# Conex_o_Motor.net
KiCad netlist of a schematic drawn in EAGLE
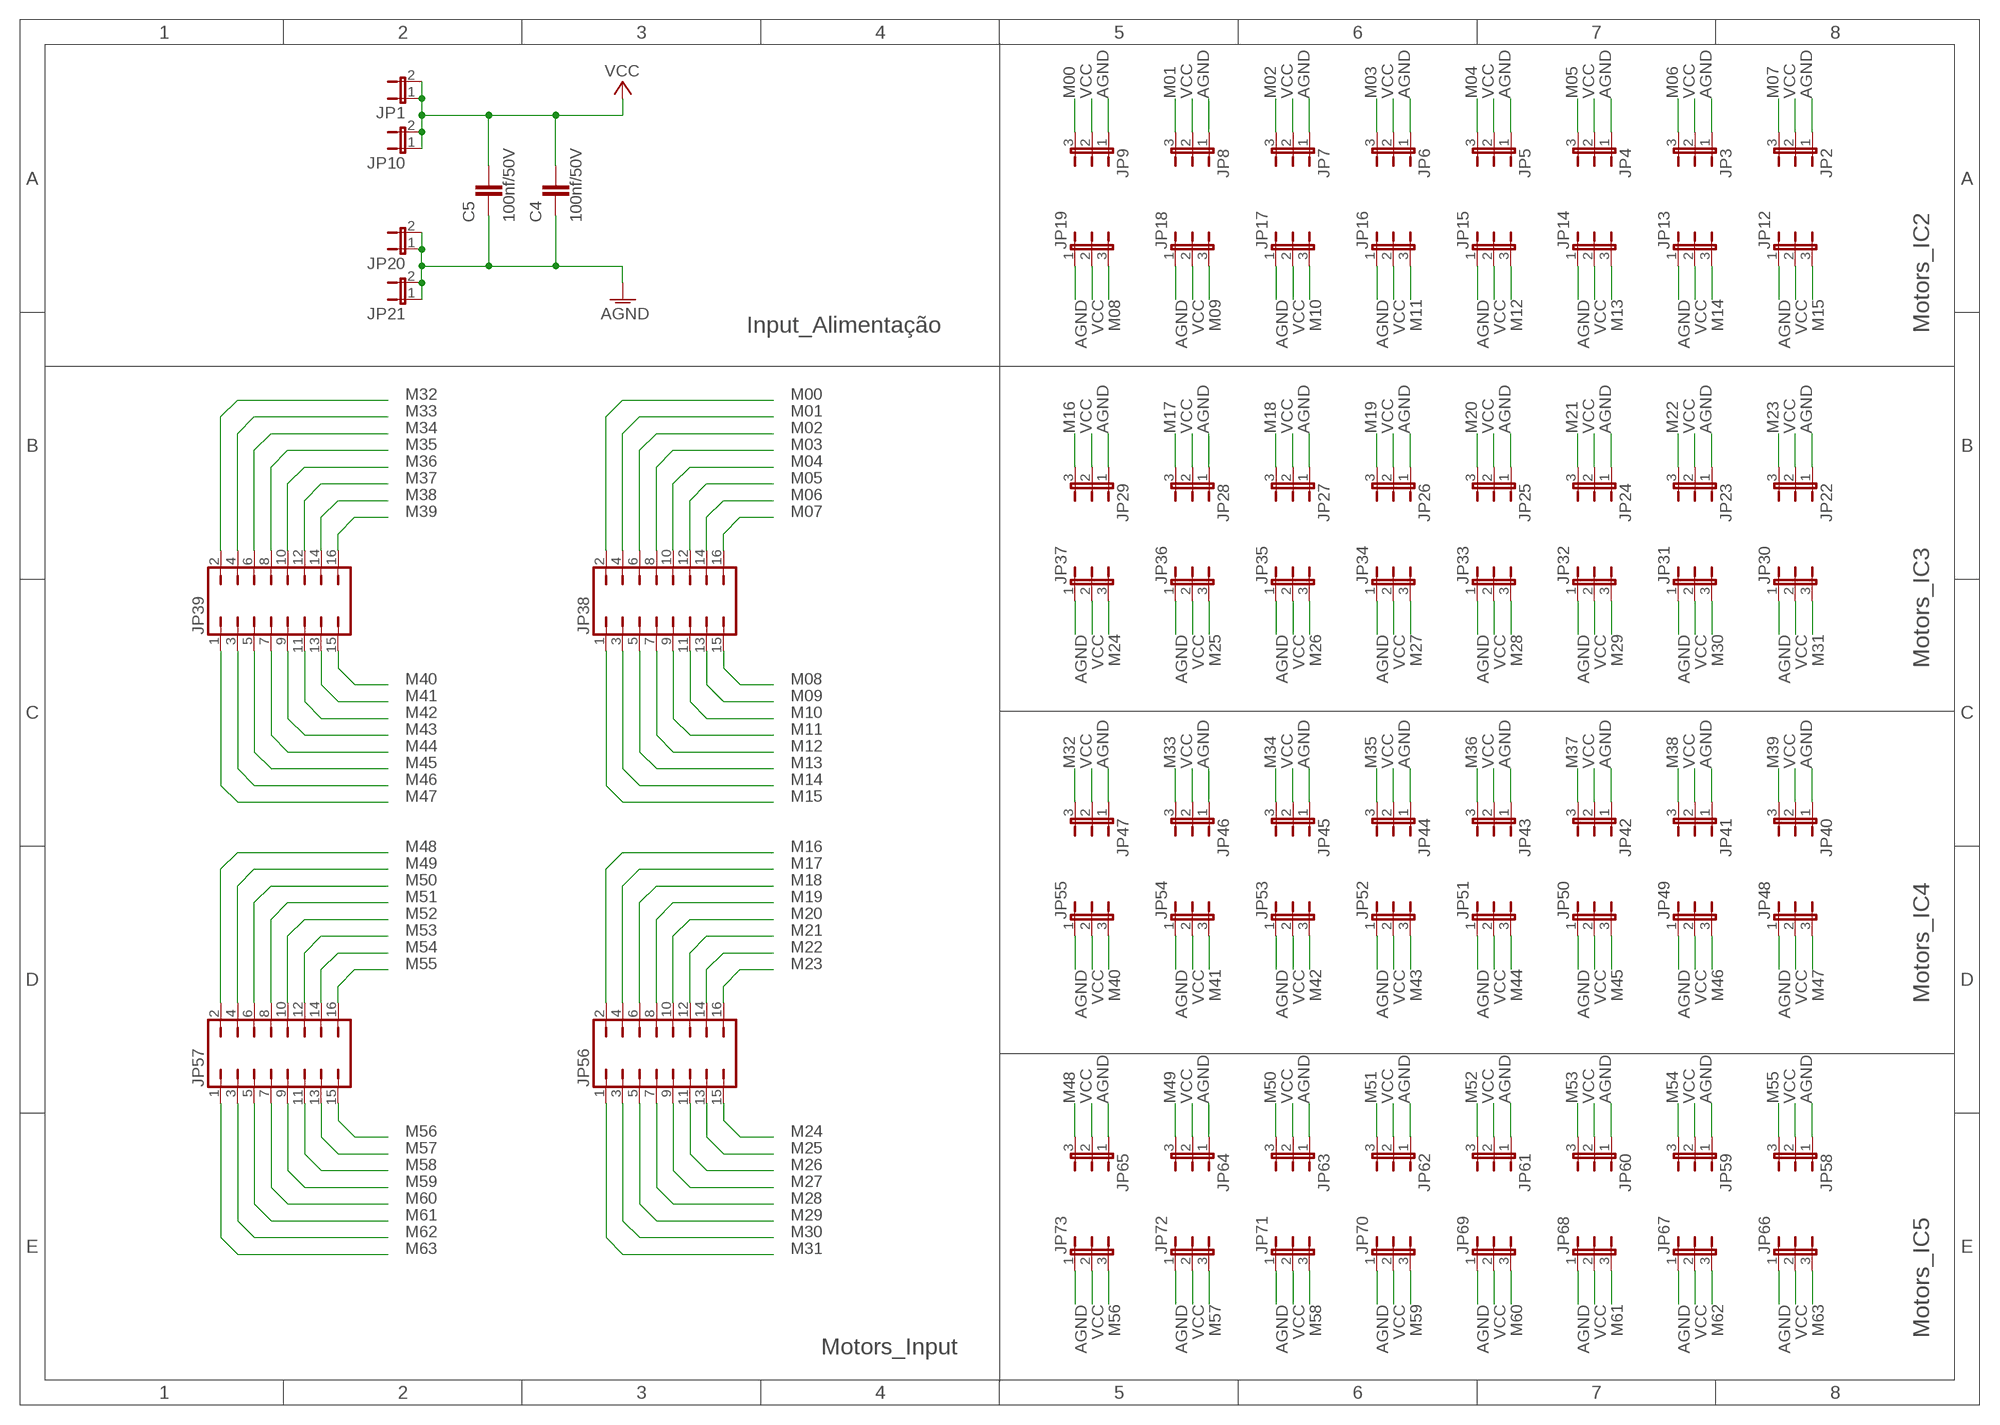
[diagram p0: schematic, sheet 1]

(export (version "E")
  (design (tool "Eeschema 10.0.6"))
  (components
    (comp (ref "C4")
      (value "100nf/50V")
      (footprint "eagle-import:C0805K")
      (libsource (lib "eagle-import") (part "C-EUC0805K"))
    )
    (comp (ref "C5")
      (value "100nf/50V")
      (footprint "eagle-import:C0805K")
      (libsource (lib "eagle-import") (part "C-EUC0805K"))
    )
    (comp (ref "JP1")
      (value "JP1E")
      (footprint "eagle-import:JP1")
      (libsource (lib "eagle-import") (part "JP1E"))
    )
    (comp (ref "JP2")
      (value "JP2E")
      (footprint "eagle-import:JP2")
      (libsource (lib "eagle-import") (part "JP2E"))
    )
    (comp (ref "JP3")
      (value "JP2E")
      (footprint "eagle-import:JP2")
      (libsource (lib "eagle-import") (part "JP2E"))
    )
    (comp (ref "JP4")
      (value "JP2E")
      (footprint "eagle-import:JP2")
      (libsource (lib "eagle-import") (part "JP2E"))
    )
    (comp (ref "JP5")
      (value "JP2E")
      (footprint "eagle-import:JP2")
      (libsource (lib "eagle-import") (part "JP2E"))
    )
    (comp (ref "JP6")
      (value "JP2E")
      (footprint "eagle-import:JP2")
      (libsource (lib "eagle-import") (part "JP2E"))
    )
    (comp (ref "JP7")
      (value "JP2E")
      (footprint "eagle-import:JP2")
      (libsource (lib "eagle-import") (part "JP2E"))
    )
    (comp (ref "JP8")
      (value "JP2E")
      (footprint "eagle-import:JP2")
      (libsource (lib "eagle-import") (part "JP2E"))
    )
    (comp (ref "JP9")
      (value "JP2E")
      (footprint "eagle-import:JP2")
      (libsource (lib "eagle-import") (part "JP2E"))
    )
    (comp (ref "JP10")
      (value "JP1E")
      (footprint "eagle-import:JP1")
      (libsource (lib "eagle-import") (part "JP1E"))
    )
    (comp (ref "JP12")
      (value "JP2E")
      (footprint "eagle-import:JP2")
      (libsource (lib "eagle-import") (part "JP2E"))
    )
    (comp (ref "JP13")
      (value "JP2E")
      (footprint "eagle-import:JP2")
      (libsource (lib "eagle-import") (part "JP2E"))
    )
    (comp (ref "JP14")
      (value "JP2E")
      (footprint "eagle-import:JP2")
      (libsource (lib "eagle-import") (part "JP2E"))
    )
    (comp (ref "JP15")
      (value "JP2E")
      (footprint "eagle-import:JP2")
      (libsource (lib "eagle-import") (part "JP2E"))
    )
    (comp (ref "JP16")
      (value "JP2E")
      (footprint "eagle-import:JP2")
      (libsource (lib "eagle-import") (part "JP2E"))
    )
    (comp (ref "JP17")
      (value "JP2E")
      (footprint "eagle-import:JP2")
      (libsource (lib "eagle-import") (part "JP2E"))
    )
    (comp (ref "JP18")
      (value "JP2E")
      (footprint "eagle-import:JP2")
      (libsource (lib "eagle-import") (part "JP2E"))
    )
    (comp (ref "JP19")
      (value "JP2E")
      (footprint "eagle-import:JP2")
      (libsource (lib "eagle-import") (part "JP2E"))
    )
    (comp (ref "JP20")
      (value "JP1E")
      (footprint "eagle-import:JP1")
      (libsource (lib "eagle-import") (part "JP1E"))
    )
    (comp (ref "JP21")
      (value "JP1E")
      (footprint "eagle-import:JP1")
      (libsource (lib "eagle-import") (part "JP1E"))
    )
    (comp (ref "JP22")
      (value "JP2E")
      (footprint "eagle-import:JP2")
      (libsource (lib "eagle-import") (part "JP2E"))
    )
    (comp (ref "JP23")
      (value "JP2E")
      (footprint "eagle-import:JP2")
      (libsource (lib "eagle-import") (part "JP2E"))
    )
    (comp (ref "JP24")
      (value "JP2E")
      (footprint "eagle-import:JP2")
      (libsource (lib "eagle-import") (part "JP2E"))
    )
    (comp (ref "JP25")
      (value "JP2E")
      (footprint "eagle-import:JP2")
      (libsource (lib "eagle-import") (part "JP2E"))
    )
    (comp (ref "JP26")
      (value "JP2E")
      (footprint "eagle-import:JP2")
      (libsource (lib "eagle-import") (part "JP2E"))
    )
    (comp (ref "JP27")
      (value "JP2E")
      (footprint "eagle-import:JP2")
      (libsource (lib "eagle-import") (part "JP2E"))
    )
    (comp (ref "JP28")
      (value "JP2E")
      (footprint "eagle-import:JP2")
      (libsource (lib "eagle-import") (part "JP2E"))
    )
    (comp (ref "JP29")
      (value "JP2E")
      (footprint "eagle-import:JP2")
      (libsource (lib "eagle-import") (part "JP2E"))
    )
    (comp (ref "JP30")
      (value "JP2E")
      (footprint "eagle-import:JP2")
      (libsource (lib "eagle-import") (part "JP2E"))
    )
    (comp (ref "JP31")
      (value "JP2E")
      (footprint "eagle-import:JP2")
      (libsource (lib "eagle-import") (part "JP2E"))
    )
    (comp (ref "JP32")
      (value "JP2E")
      (footprint "eagle-import:JP2")
      (libsource (lib "eagle-import") (part "JP2E"))
    )
    (comp (ref "JP33")
      (value "JP2E")
      (footprint "eagle-import:JP2")
      (libsource (lib "eagle-import") (part "JP2E"))
    )
    (comp (ref "JP34")
      (value "JP2E")
      (footprint "eagle-import:JP2")
      (libsource (lib "eagle-import") (part "JP2E"))
    )
    (comp (ref "JP35")
      (value "JP2E")
      (footprint "eagle-import:JP2")
      (libsource (lib "eagle-import") (part "JP2E"))
    )
    (comp (ref "JP36")
      (value "JP2E")
      (footprint "eagle-import:JP2")
      (libsource (lib "eagle-import") (part "JP2E"))
    )
    (comp (ref "JP37")
      (value "JP2E")
      (footprint "eagle-import:JP2")
      (libsource (lib "eagle-import") (part "JP2E"))
    )
    (comp (ref "JP38")
      (value "JP8Q")
      (footprint "eagle-import:JP8Q")
      (libsource (lib "eagle-import") (part "JP8Q"))
    )
    (comp (ref "JP39")
      (value "JP8Q")
      (footprint "eagle-import:JP8Q")
      (libsource (lib "eagle-import") (part "JP8Q"))
    )
    (comp (ref "JP40")
      (value "JP2E")
      (footprint "eagle-import:JP2")
      (libsource (lib "eagle-import") (part "JP2E"))
    )
    (comp (ref "JP41")
      (value "JP2E")
      (footprint "eagle-import:JP2")
      (libsource (lib "eagle-import") (part "JP2E"))
    )
    (comp (ref "JP42")
      (value "JP2E")
      (footprint "eagle-import:JP2")
      (libsource (lib "eagle-import") (part "JP2E"))
    )
    (comp (ref "JP43")
      (value "JP2E")
      (footprint "eagle-import:JP2")
      (libsource (lib "eagle-import") (part "JP2E"))
    )
    (comp (ref "JP44")
      (value "JP2E")
      (footprint "eagle-import:JP2")
      (libsource (lib "eagle-import") (part "JP2E"))
    )
    (comp (ref "JP45")
      (value "JP2E")
      (footprint "eagle-import:JP2")
      (libsource (lib "eagle-import") (part "JP2E"))
    )
    (comp (ref "JP46")
      (value "JP2E")
      (footprint "eagle-import:JP2")
      (libsource (lib "eagle-import") (part "JP2E"))
    )
    (comp (ref "JP47")
      (value "JP2E")
      (footprint "eagle-import:JP2")
      (libsource (lib "eagle-import") (part "JP2E"))
    )
    (comp (ref "JP48")
      (value "JP2E")
      (footprint "eagle-import:JP2")
      (libsource (lib "eagle-import") (part "JP2E"))
    )
    (comp (ref "JP49")
      (value "JP2E")
      (footprint "eagle-import:JP2")
      (libsource (lib "eagle-import") (part "JP2E"))
    )
    (comp (ref "JP50")
      (value "JP2E")
      (footprint "eagle-import:JP2")
      (libsource (lib "eagle-import") (part "JP2E"))
    )
    (comp (ref "JP51")
      (value "JP2E")
      (footprint "eagle-import:JP2")
      (libsource (lib "eagle-import") (part "JP2E"))
    )
    (comp (ref "JP52")
      (value "JP2E")
      (footprint "eagle-import:JP2")
      (libsource (lib "eagle-import") (part "JP2E"))
    )
    (comp (ref "JP53")
      (value "JP2E")
      (footprint "eagle-import:JP2")
      (libsource (lib "eagle-import") (part "JP2E"))
    )
    (comp (ref "JP54")
      (value "JP2E")
      (footprint "eagle-import:JP2")
      (libsource (lib "eagle-import") (part "JP2E"))
    )
    (comp (ref "JP55")
      (value "JP2E")
      (footprint "eagle-import:JP2")
      (libsource (lib "eagle-import") (part "JP2E"))
    )
    (comp (ref "JP56")
      (value "JP8Q")
      (footprint "eagle-import:JP8Q")
      (libsource (lib "eagle-import") (part "JP8Q"))
    )
    (comp (ref "JP57")
      (value "JP8Q")
      (footprint "eagle-import:JP8Q")
      (libsource (lib "eagle-import") (part "JP8Q"))
    )
    (comp (ref "JP58")
      (value "JP2E")
      (footprint "eagle-import:JP2")
      (libsource (lib "eagle-import") (part "JP2E"))
    )
    (comp (ref "JP59")
      (value "JP2E")
      (footprint "eagle-import:JP2")
      (libsource (lib "eagle-import") (part "JP2E"))
    )
    (comp (ref "JP60")
      (value "JP2E")
      (footprint "eagle-import:JP2")
      (libsource (lib "eagle-import") (part "JP2E"))
    )
    (comp (ref "JP61")
      (value "JP2E")
      (footprint "eagle-import:JP2")
      (libsource (lib "eagle-import") (part "JP2E"))
    )
    (comp (ref "JP62")
      (value "JP2E")
      (footprint "eagle-import:JP2")
      (libsource (lib "eagle-import") (part "JP2E"))
    )
    (comp (ref "JP63")
      (value "JP2E")
      (footprint "eagle-import:JP2")
      (libsource (lib "eagle-import") (part "JP2E"))
    )
    (comp (ref "JP64")
      (value "JP2E")
      (footprint "eagle-import:JP2")
      (libsource (lib "eagle-import") (part "JP2E"))
    )
    (comp (ref "JP65")
      (value "JP2E")
      (footprint "eagle-import:JP2")
      (libsource (lib "eagle-import") (part "JP2E"))
    )
    (comp (ref "JP66")
      (value "JP2E")
      (footprint "eagle-import:JP2")
      (libsource (lib "eagle-import") (part "JP2E"))
    )
    (comp (ref "JP67")
      (value "JP2E")
      (footprint "eagle-import:JP2")
      (libsource (lib "eagle-import") (part "JP2E"))
    )
    (comp (ref "JP68")
      (value "JP2E")
      (footprint "eagle-import:JP2")
      (libsource (lib "eagle-import") (part "JP2E"))
    )
    (comp (ref "JP69")
      (value "JP2E")
      (footprint "eagle-import:JP2")
      (libsource (lib "eagle-import") (part "JP2E"))
    )
    (comp (ref "JP70")
      (value "JP2E")
      (footprint "eagle-import:JP2")
      (libsource (lib "eagle-import") (part "JP2E"))
    )
    (comp (ref "JP71")
      (value "JP2E")
      (footprint "eagle-import:JP2")
      (libsource (lib "eagle-import") (part "JP2E"))
    )
    (comp (ref "JP72")
      (value "JP2E")
      (footprint "eagle-import:JP2")
      (libsource (lib "eagle-import") (part "JP2E"))
    )
    (comp (ref "JP73")
      (value "JP2E")
      (footprint "eagle-import:JP2")
      (libsource (lib "eagle-import") (part "JP2E"))
    )
  )
  (nets
    (net (code "1") (name "/M00") (class "Default")
      (node (ref "JP38") (pin "2") (pinfunction "2_2") (pintype "passive"))
      (node (ref "JP9") (pin "3") (pinfunction "3_3") (pintype "passive"))
    )
    (net (code "2") (name "/M01") (class "Default")
      (node (ref "JP38") (pin "4") (pinfunction "4_4") (pintype "passive"))
      (node (ref "JP8") (pin "3") (pinfunction "3_3") (pintype "passive"))
    )
    (net (code "3") (name "/M02") (class "Default")
      (node (ref "JP38") (pin "6") (pinfunction "6_6") (pintype "passive"))
      (node (ref "JP7") (pin "3") (pinfunction "3_3") (pintype "passive"))
    )
    (net (code "4") (name "/M03") (class "Default")
      (node (ref "JP38") (pin "8") (pinfunction "8_8") (pintype "passive"))
      (node (ref "JP6") (pin "3") (pinfunction "3_3") (pintype "passive"))
    )
    (net (code "5") (name "/M04") (class "Default")
      (node (ref "JP38") (pin "10") (pinfunction "10_10") (pintype "passive"))
      (node (ref "JP5") (pin "3") (pinfunction "3_3") (pintype "passive"))
    )
    (net (code "6") (name "/M05") (class "Default")
      (node (ref "JP38") (pin "12") (pinfunction "12_12") (pintype "passive"))
      (node (ref "JP4") (pin "3") (pinfunction "3_3") (pintype "passive"))
    )
    (net (code "7") (name "/M06") (class "Default")
      (node (ref "JP3") (pin "3") (pinfunction "3_3") (pintype "passive"))
      (node (ref "JP38") (pin "14") (pinfunction "14_14") (pintype "passive"))
    )
    (net (code "8") (name "/M07") (class "Default")
      (node (ref "JP2") (pin "3") (pinfunction "3_3") (pintype "passive"))
      (node (ref "JP38") (pin "16") (pinfunction "16_16") (pintype "passive"))
    )
    (net (code "9") (name "/M08") (class "Default")
      (node (ref "JP19") (pin "3") (pinfunction "3_3") (pintype "passive"))
      (node (ref "JP38") (pin "15") (pinfunction "15_15") (pintype "passive"))
    )
    (net (code "10") (name "/M09") (class "Default")
      (node (ref "JP18") (pin "3") (pinfunction "3_3") (pintype "passive"))
      (node (ref "JP38") (pin "13") (pinfunction "13_13") (pintype "passive"))
    )
    (net (code "11") (name "/M10") (class "Default")
      (node (ref "JP17") (pin "3") (pinfunction "3_3") (pintype "passive"))
      (node (ref "JP38") (pin "11") (pinfunction "11_11") (pintype "passive"))
    )
    (net (code "12") (name "/M11") (class "Default")
      (node (ref "JP16") (pin "3") (pinfunction "3_3") (pintype "passive"))
      (node (ref "JP38") (pin "9") (pinfunction "9_9") (pintype "passive"))
    )
    (net (code "13") (name "/M12") (class "Default")
      (node (ref "JP15") (pin "3") (pinfunction "3_3") (pintype "passive"))
      (node (ref "JP38") (pin "7") (pinfunction "7_7") (pintype "passive"))
    )
    (net (code "14") (name "/M13") (class "Default")
      (node (ref "JP14") (pin "3") (pinfunction "3_3") (pintype "passive"))
      (node (ref "JP38") (pin "5") (pinfunction "5_5") (pintype "passive"))
    )
    (net (code "15") (name "/M14") (class "Default")
      (node (ref "JP13") (pin "3") (pinfunction "3_3") (pintype "passive"))
      (node (ref "JP38") (pin "3") (pinfunction "3_3") (pintype "passive"))
    )
    (net (code "16") (name "/M15") (class "Default")
      (node (ref "JP12") (pin "3") (pinfunction "3_3") (pintype "passive"))
      (node (ref "JP38") (pin "1") (pinfunction "1_1") (pintype "passive"))
    )
    (net (code "17") (name "/M16") (class "Default")
      (node (ref "JP29") (pin "3") (pinfunction "3_3") (pintype "passive"))
      (node (ref "JP56") (pin "2") (pinfunction "2_2") (pintype "passive"))
    )
    (net (code "18") (name "/M17") (class "Default")
      (node (ref "JP28") (pin "3") (pinfunction "3_3") (pintype "passive"))
      (node (ref "JP56") (pin "4") (pinfunction "4_4") (pintype "passive"))
    )
    (net (code "19") (name "/M18") (class "Default")
      (node (ref "JP27") (pin "3") (pinfunction "3_3") (pintype "passive"))
      (node (ref "JP56") (pin "6") (pinfunction "6_6") (pintype "passive"))
    )
    (net (code "20") (name "/M19") (class "Default")
      (node (ref "JP26") (pin "3") (pinfunction "3_3") (pintype "passive"))
      (node (ref "JP56") (pin "8") (pinfunction "8_8") (pintype "passive"))
    )
    (net (code "21") (name "/M20") (class "Default")
      (node (ref "JP25") (pin "3") (pinfunction "3_3") (pintype "passive"))
      (node (ref "JP56") (pin "10") (pinfunction "10_10") (pintype "passive"))
    )
    (net (code "22") (name "/M21") (class "Default")
      (node (ref "JP24") (pin "3") (pinfunction "3_3") (pintype "passive"))
      (node (ref "JP56") (pin "12") (pinfunction "12_12") (pintype "passive"))
    )
    (net (code "23") (name "/M22") (class "Default")
      (node (ref "JP23") (pin "3") (pinfunction "3_3") (pintype "passive"))
      (node (ref "JP56") (pin "14") (pinfunction "14_14") (pintype "passive"))
    )
    (net (code "24") (name "/M23") (class "Default")
      (node (ref "JP22") (pin "3") (pinfunction "3_3") (pintype "passive"))
      (node (ref "JP56") (pin "16") (pinfunction "16_16") (pintype "passive"))
    )
    (net (code "25") (name "/M24") (class "Default")
      (node (ref "JP37") (pin "3") (pinfunction "3_3") (pintype "passive"))
      (node (ref "JP56") (pin "15") (pinfunction "15_15") (pintype "passive"))
    )
    (net (code "26") (name "/M25") (class "Default")
      (node (ref "JP36") (pin "3") (pinfunction "3_3") (pintype "passive"))
      (node (ref "JP56") (pin "13") (pinfunction "13_13") (pintype "passive"))
    )
    (net (code "27") (name "/M26") (class "Default")
      (node (ref "JP35") (pin "3") (pinfunction "3_3") (pintype "passive"))
      (node (ref "JP56") (pin "11") (pinfunction "11_11") (pintype "passive"))
    )
    (net (code "28") (name "/M27") (class "Default")
      (node (ref "JP34") (pin "3") (pinfunction "3_3") (pintype "passive"))
      (node (ref "JP56") (pin "9") (pinfunction "9_9") (pintype "passive"))
    )
    (net (code "29") (name "/M28") (class "Default")
      (node (ref "JP33") (pin "3") (pinfunction "3_3") (pintype "passive"))
      (node (ref "JP56") (pin "7") (pinfunction "7_7") (pintype "passive"))
    )
    (net (code "30") (name "/M29") (class "Default")
      (node (ref "JP32") (pin "3") (pinfunction "3_3") (pintype "passive"))
      (node (ref "JP56") (pin "5") (pinfunction "5_5") (pintype "passive"))
    )
    (net (code "31") (name "/M30") (class "Default")
      (node (ref "JP31") (pin "3") (pinfunction "3_3") (pintype "passive"))
      (node (ref "JP56") (pin "3") (pinfunction "3_3") (pintype "passive"))
    )
    (net (code "32") (name "/M31") (class "Default")
      (node (ref "JP30") (pin "3") (pinfunction "3_3") (pintype "passive"))
      (node (ref "JP56") (pin "1") (pinfunction "1_1") (pintype "passive"))
    )
    (net (code "33") (name "/M32") (class "Default")
      (node (ref "JP39") (pin "2") (pinfunction "2_2") (pintype "passive"))
      (node (ref "JP47") (pin "3") (pinfunction "3_3") (pintype "passive"))
    )
    (net (code "34") (name "/M33") (class "Default")
      (node (ref "JP39") (pin "4") (pinfunction "4_4") (pintype "passive"))
      (node (ref "JP46") (pin "3") (pinfunction "3_3") (pintype "passive"))
    )
    (net (code "35") (name "/M34") (class "Default")
      (node (ref "JP39") (pin "6") (pinfunction "6_6") (pintype "passive"))
      (node (ref "JP45") (pin "3") (pinfunction "3_3") (pintype "passive"))
    )
    (net (code "36") (name "/M35") (class "Default")
      (node (ref "JP39") (pin "8") (pinfunction "8_8") (pintype "passive"))
      (node (ref "JP44") (pin "3") (pinfunction "3_3") (pintype "passive"))
    )
    (net (code "37") (name "/M36") (class "Default")
      (node (ref "JP39") (pin "10") (pinfunction "10_10") (pintype "passive"))
      (node (ref "JP43") (pin "3") (pinfunction "3_3") (pintype "passive"))
    )
    (net (code "38") (name "/M37") (class "Default")
      (node (ref "JP39") (pin "12") (pinfunction "12_12") (pintype "passive"))
      (node (ref "JP42") (pin "3") (pinfunction "3_3") (pintype "passive"))
    )
    (net (code "39") (name "/M38") (class "Default")
      (node (ref "JP39") (pin "14") (pinfunction "14_14") (pintype "passive"))
      (node (ref "JP41") (pin "3") (pinfunction "3_3") (pintype "passive"))
    )
    (net (code "40") (name "/M39") (class "Default")
      (node (ref "JP39") (pin "16") (pinfunction "16_16") (pintype "passive"))
      (node (ref "JP40") (pin "3") (pinfunction "3_3") (pintype "passive"))
    )
    (net (code "41") (name "/M40") (class "Default")
      (node (ref "JP39") (pin "15") (pinfunction "15_15") (pintype "passive"))
      (node (ref "JP55") (pin "3") (pinfunction "3_3") (pintype "passive"))
    )
    (net (code "42") (name "/M41") (class "Default")
      (node (ref "JP39") (pin "13") (pinfunction "13_13") (pintype "passive"))
      (node (ref "JP54") (pin "3") (pinfunction "3_3") (pintype "passive"))
    )
    (net (code "43") (name "/M42") (class "Default")
      (node (ref "JP39") (pin "11") (pinfunction "11_11") (pintype "passive"))
      (node (ref "JP53") (pin "3") (pinfunction "3_3") (pintype "passive"))
    )
    (net (code "44") (name "/M43") (class "Default")
      (node (ref "JP39") (pin "9") (pinfunction "9_9") (pintype "passive"))
      (node (ref "JP52") (pin "3") (pinfunction "3_3") (pintype "passive"))
    )
    (net (code "45") (name "/M44") (class "Default")
      (node (ref "JP39") (pin "7") (pinfunction "7_7") (pintype "passive"))
      (node (ref "JP51") (pin "3") (pinfunction "3_3") (pintype "passive"))
    )
    (net (code "46") (name "/M45") (class "Default")
      (node (ref "JP39") (pin "5") (pinfunction "5_5") (pintype "passive"))
      (node (ref "JP50") (pin "3") (pinfunction "3_3") (pintype "passive"))
    )
    (net (code "47") (name "/M46") (class "Default")
      (node (ref "JP39") (pin "3") (pinfunction "3_3") (pintype "passive"))
      (node (ref "JP49") (pin "3") (pinfunction "3_3") (pintype "passive"))
    )
    (net (code "48") (name "/M47") (class "Default")
      (node (ref "JP39") (pin "1") (pinfunction "1_1") (pintype "passive"))
      (node (ref "JP48") (pin "3") (pinfunction "3_3") (pintype "passive"))
    )
    (net (code "49") (name "/M48") (class "Default")
      (node (ref "JP57") (pin "2") (pinfunction "2_2") (pintype "passive"))
      (node (ref "JP65") (pin "3") (pinfunction "3_3") (pintype "passive"))
    )
    (net (code "50") (name "/M49") (class "Default")
      (node (ref "JP57") (pin "4") (pinfunction "4_4") (pintype "passive"))
      (node (ref "JP64") (pin "3") (pinfunction "3_3") (pintype "passive"))
    )
    (net (code "51") (name "/M50") (class "Default")
      (node (ref "JP57") (pin "6") (pinfunction "6_6") (pintype "passive"))
      (node (ref "JP63") (pin "3") (pinfunction "3_3") (pintype "passive"))
    )
    (net (code "52") (name "/M51") (class "Default")
      (node (ref "JP57") (pin "8") (pinfunction "8_8") (pintype "passive"))
      (node (ref "JP62") (pin "3") (pinfunction "3_3") (pintype "passive"))
    )
    (net (code "53") (name "/M52") (class "Default")
      (node (ref "JP57") (pin "10") (pinfunction "10_10") (pintype "passive"))
      (node (ref "JP61") (pin "3") (pinfunction "3_3") (pintype "passive"))
    )
    (net (code "54") (name "/M53") (class "Default")
      (node (ref "JP57") (pin "12") (pinfunction "12_12") (pintype "passive"))
      (node (ref "JP60") (pin "3") (pinfunction "3_3") (pintype "passive"))
    )
    (net (code "55") (name "/M54") (class "Default")
      (node (ref "JP57") (pin "14") (pinfunction "14_14") (pintype "passive"))
      (node (ref "JP59") (pin "3") (pinfunction "3_3") (pintype "passive"))
    )
    (net (code "56") (name "/M55") (class "Default")
      (node (ref "JP57") (pin "16") (pinfunction "16_16") (pintype "passive"))
      (node (ref "JP58") (pin "3") (pinfunction "3_3") (pintype "passive"))
    )
    (net (code "57") (name "/M56") (class "Default")
      (node (ref "JP57") (pin "15") (pinfunction "15_15") (pintype "passive"))
      (node (ref "JP73") (pin "3") (pinfunction "3_3") (pintype "passive"))
    )
    (net (code "58") (name "/M57") (class "Default")
      (node (ref "JP57") (pin "13") (pinfunction "13_13") (pintype "passive"))
      (node (ref "JP72") (pin "3") (pinfunction "3_3") (pintype "passive"))
    )
    (net (code "59") (name "/M58") (class "Default")
      (node (ref "JP57") (pin "11") (pinfunction "11_11") (pintype "passive"))
      (node (ref "JP71") (pin "3") (pinfunction "3_3") (pintype "passive"))
    )
    (net (code "60") (name "/M59") (class "Default")
      (node (ref "JP57") (pin "9") (pinfunction "9_9") (pintype "passive"))
      (node (ref "JP70") (pin "3") (pinfunction "3_3") (pintype "passive"))
    )
    (net (code "61") (name "/M60") (class "Default")
      (node (ref "JP57") (pin "7") (pinfunction "7_7") (pintype "passive"))
      (node (ref "JP69") (pin "3") (pinfunction "3_3") (pintype "passive"))
    )
    (net (code "62") (name "/M61") (class "Default")
      (node (ref "JP57") (pin "5") (pinfunction "5_5") (pintype "passive"))
      (node (ref "JP68") (pin "3") (pinfunction "3_3") (pintype "passive"))
    )
    (net (code "63") (name "/M62") (class "Default")
      (node (ref "JP57") (pin "3") (pinfunction "3_3") (pintype "passive"))
      (node (ref "JP67") (pin "3") (pinfunction "3_3") (pintype "passive"))
    )
    (net (code "64") (name "/M63") (class "Default")
      (node (ref "JP57") (pin "1") (pinfunction "1_1") (pintype "passive"))
      (node (ref "JP66") (pin "3") (pinfunction "3_3") (pintype "passive"))
    )
    (net (code "65") (name "AGND") (class "Default")
      (node (ref "C4") (pin "2") (pinfunction "2_2") (pintype "passive"))
      (node (ref "C5") (pin "2") (pinfunction "2_2") (pintype "passive"))
      (node (ref "JP12") (pin "1") (pinfunction "1_1") (pintype "passive"))
      (node (ref "JP13") (pin "1") (pinfunction "1_1") (pintype "passive"))
      (node (ref "JP14") (pin "1") (pinfunction "1_1") (pintype "passive"))
      (node (ref "JP15") (pin "1") (pinfunction "1_1") (pintype "passive"))
      (node (ref "JP16") (pin "1") (pinfunction "1_1") (pintype "passive"))
      (node (ref "JP17") (pin "1") (pinfunction "1_1") (pintype "passive"))
      (node (ref "JP18") (pin "1") (pinfunction "1_1") (pintype "passive"))
      (node (ref "JP19") (pin "1") (pinfunction "1_1") (pintype "passive"))
      (node (ref "JP2") (pin "1") (pinfunction "1_1") (pintype "passive"))
      (node (ref "JP20") (pin "1") (pinfunction "1_1") (pintype "passive"))
      (node (ref "JP20") (pin "2") (pinfunction "2_2") (pintype "passive"))
      (node (ref "JP21") (pin "1") (pinfunction "1_1") (pintype "passive"))
      (node (ref "JP21") (pin "2") (pinfunction "2_2") (pintype "passive"))
      (node (ref "JP22") (pin "1") (pinfunction "1_1") (pintype "passive"))
      (node (ref "JP23") (pin "1") (pinfunction "1_1") (pintype "passive"))
      (node (ref "JP24") (pin "1") (pinfunction "1_1") (pintype "passive"))
      (node (ref "JP25") (pin "1") (pinfunction "1_1") (pintype "passive"))
      (node (ref "JP26") (pin "1") (pinfunction "1_1") (pintype "passive"))
      (node (ref "JP27") (pin "1") (pinfunction "1_1") (pintype "passive"))
      (node (ref "JP28") (pin "1") (pinfunction "1_1") (pintype "passive"))
      (node (ref "JP29") (pin "1") (pinfunction "1_1") (pintype "passive"))
      (node (ref "JP3") (pin "1") (pinfunction "1_1") (pintype "passive"))
      (node (ref "JP30") (pin "1") (pinfunction "1_1") (pintype "passive"))
      (node (ref "JP31") (pin "1") (pinfunction "1_1") (pintype "passive"))
      (node (ref "JP32") (pin "1") (pinfunction "1_1") (pintype "passive"))
      (node (ref "JP33") (pin "1") (pinfunction "1_1") (pintype "passive"))
      (node (ref "JP34") (pin "1") (pinfunction "1_1") (pintype "passive"))
      (node (ref "JP35") (pin "1") (pinfunction "1_1") (pintype "passive"))
      (node (ref "JP36") (pin "1") (pinfunction "1_1") (pintype "passive"))
      (node (ref "JP37") (pin "1") (pinfunction "1_1") (pintype "passive"))
      (node (ref "JP4") (pin "1") (pinfunction "1_1") (pintype "passive"))
      (node (ref "JP40") (pin "1") (pinfunction "1_1") (pintype "passive"))
      (node (ref "JP41") (pin "1") (pinfunction "1_1") (pintype "passive"))
      (node (ref "JP42") (pin "1") (pinfunction "1_1") (pintype "passive"))
      (node (ref "JP43") (pin "1") (pinfunction "1_1") (pintype "passive"))
      (node (ref "JP44") (pin "1") (pinfunction "1_1") (pintype "passive"))
      (node (ref "JP45") (pin "1") (pinfunction "1_1") (pintype "passive"))
      (node (ref "JP46") (pin "1") (pinfunction "1_1") (pintype "passive"))
      (node (ref "JP47") (pin "1") (pinfunction "1_1") (pintype "passive"))
      (node (ref "JP48") (pin "1") (pinfunction "1_1") (pintype "passive"))
      (node (ref "JP49") (pin "1") (pinfunction "1_1") (pintype "passive"))
      (node (ref "JP5") (pin "1") (pinfunction "1_1") (pintype "passive"))
      (node (ref "JP50") (pin "1") (pinfunction "1_1") (pintype "passive"))
      (node (ref "JP51") (pin "1") (pinfunction "1_1") (pintype "passive"))
      (node (ref "JP52") (pin "1") (pinfunction "1_1") (pintype "passive"))
      (node (ref "JP53") (pin "1") (pinfunction "1_1") (pintype "passive"))
      (node (ref "JP54") (pin "1") (pinfunction "1_1") (pintype "passive"))
      (node (ref "JP55") (pin "1") (pinfunction "1_1") (pintype "passive"))
      (node (ref "JP58") (pin "1") (pinfunction "1_1") (pintype "passive"))
      (node (ref "JP59") (pin "1") (pinfunction "1_1") (pintype "passive"))
      (node (ref "JP6") (pin "1") (pinfunction "1_1") (pintype "passive"))
      (node (ref "JP60") (pin "1") (pinfunction "1_1") (pintype "passive"))
      (node (ref "JP61") (pin "1") (pinfunction "1_1") (pintype "passive"))
      (node (ref "JP62") (pin "1") (pinfunction "1_1") (pintype "passive"))
      (node (ref "JP63") (pin "1") (pinfunction "1_1") (pintype "passive"))
      (node (ref "JP64") (pin "1") (pinfunction "1_1") (pintype "passive"))
      (node (ref "JP65") (pin "1") (pinfunction "1_1") (pintype "passive"))
      (node (ref "JP66") (pin "1") (pinfunction "1_1") (pintype "passive"))
      (node (ref "JP67") (pin "1") (pinfunction "1_1") (pintype "passive"))
      (node (ref "JP68") (pin "1") (pinfunction "1_1") (pintype "passive"))
      (node (ref "JP69") (pin "1") (pinfunction "1_1") (pintype "passive"))
      (node (ref "JP7") (pin "1") (pinfunction "1_1") (pintype "passive"))
      (node (ref "JP70") (pin "1") (pinfunction "1_1") (pintype "passive"))
      (node (ref "JP71") (pin "1") (pinfunction "1_1") (pintype "passive"))
      (node (ref "JP72") (pin "1") (pinfunction "1_1") (pintype "passive"))
      (node (ref "JP73") (pin "1") (pinfunction "1_1") (pintype "passive"))
      (node (ref "JP8") (pin "1") (pinfunction "1_1") (pintype "passive"))
      (node (ref "JP9") (pin "1") (pinfunction "1_1") (pintype "passive"))
    )
    (net (code "66") (name "VCC") (class "Default")
      (node (ref "C4") (pin "1") (pinfunction "1_1") (pintype "passive"))
      (node (ref "C5") (pin "1") (pinfunction "1_1") (pintype "passive"))
      (node (ref "JP1") (pin "1") (pinfunction "1_1") (pintype "passive"))
      (node (ref "JP1") (pin "2") (pinfunction "2_2") (pintype "passive"))
      (node (ref "JP10") (pin "1") (pinfunction "1_1") (pintype "passive"))
      (node (ref "JP10") (pin "2") (pinfunction "2_2") (pintype "passive"))
      (node (ref "JP12") (pin "2") (pinfunction "2_2") (pintype "passive"))
      (node (ref "JP13") (pin "2") (pinfunction "2_2") (pintype "passive"))
      (node (ref "JP14") (pin "2") (pinfunction "2_2") (pintype "passive"))
      (node (ref "JP15") (pin "2") (pinfunction "2_2") (pintype "passive"))
      (node (ref "JP16") (pin "2") (pinfunction "2_2") (pintype "passive"))
      (node (ref "JP17") (pin "2") (pinfunction "2_2") (pintype "passive"))
      (node (ref "JP18") (pin "2") (pinfunction "2_2") (pintype "passive"))
      (node (ref "JP19") (pin "2") (pinfunction "2_2") (pintype "passive"))
      (node (ref "JP2") (pin "2") (pinfunction "2_2") (pintype "passive"))
      (node (ref "JP22") (pin "2") (pinfunction "2_2") (pintype "passive"))
      (node (ref "JP23") (pin "2") (pinfunction "2_2") (pintype "passive"))
      (node (ref "JP24") (pin "2") (pinfunction "2_2") (pintype "passive"))
      (node (ref "JP25") (pin "2") (pinfunction "2_2") (pintype "passive"))
      (node (ref "JP26") (pin "2") (pinfunction "2_2") (pintype "passive"))
      (node (ref "JP27") (pin "2") (pinfunction "2_2") (pintype "passive"))
      (node (ref "JP28") (pin "2") (pinfunction "2_2") (pintype "passive"))
      (node (ref "JP29") (pin "2") (pinfunction "2_2") (pintype "passive"))
      (node (ref "JP3") (pin "2") (pinfunction "2_2") (pintype "passive"))
      (node (ref "JP30") (pin "2") (pinfunction "2_2") (pintype "passive"))
      (node (ref "JP31") (pin "2") (pinfunction "2_2") (pintype "passive"))
      (node (ref "JP32") (pin "2") (pinfunction "2_2") (pintype "passive"))
      (node (ref "JP33") (pin "2") (pinfunction "2_2") (pintype "passive"))
      (node (ref "JP34") (pin "2") (pinfunction "2_2") (pintype "passive"))
      (node (ref "JP35") (pin "2") (pinfunction "2_2") (pintype "passive"))
      (node (ref "JP36") (pin "2") (pinfunction "2_2") (pintype "passive"))
      (node (ref "JP37") (pin "2") (pinfunction "2_2") (pintype "passive"))
      (node (ref "JP4") (pin "2") (pinfunction "2_2") (pintype "passive"))
      (node (ref "JP40") (pin "2") (pinfunction "2_2") (pintype "passive"))
      (node (ref "JP41") (pin "2") (pinfunction "2_2") (pintype "passive"))
      (node (ref "JP42") (pin "2") (pinfunction "2_2") (pintype "passive"))
      (node (ref "JP43") (pin "2") (pinfunction "2_2") (pintype "passive"))
      (node (ref "JP44") (pin "2") (pinfunction "2_2") (pintype "passive"))
      (node (ref "JP45") (pin "2") (pinfunction "2_2") (pintype "passive"))
      (node (ref "JP46") (pin "2") (pinfunction "2_2") (pintype "passive"))
      (node (ref "JP47") (pin "2") (pinfunction "2_2") (pintype "passive"))
      (node (ref "JP48") (pin "2") (pinfunction "2_2") (pintype "passive"))
      (node (ref "JP49") (pin "2") (pinfunction "2_2") (pintype "passive"))
      (node (ref "JP5") (pin "2") (pinfunction "2_2") (pintype "passive"))
      (node (ref "JP50") (pin "2") (pinfunction "2_2") (pintype "passive"))
      (node (ref "JP51") (pin "2") (pinfunction "2_2") (pintype "passive"))
      (node (ref "JP52") (pin "2") (pinfunction "2_2") (pintype "passive"))
      (node (ref "JP53") (pin "2") (pinfunction "2_2") (pintype "passive"))
      (node (ref "JP54") (pin "2") (pinfunction "2_2") (pintype "passive"))
      (node (ref "JP55") (pin "2") (pinfunction "2_2") (pintype "passive"))
      (node (ref "JP58") (pin "2") (pinfunction "2_2") (pintype "passive"))
      (node (ref "JP59") (pin "2") (pinfunction "2_2") (pintype "passive"))
      (node (ref "JP6") (pin "2") (pinfunction "2_2") (pintype "passive"))
      (node (ref "JP60") (pin "2") (pinfunction "2_2") (pintype "passive"))
      (node (ref "JP61") (pin "2") (pinfunction "2_2") (pintype "passive"))
      (node (ref "JP62") (pin "2") (pinfunction "2_2") (pintype "passive"))
      (node (ref "JP63") (pin "2") (pinfunction "2_2") (pintype "passive"))
      (node (ref "JP64") (pin "2") (pinfunction "2_2") (pintype "passive"))
      (node (ref "JP65") (pin "2") (pinfunction "2_2") (pintype "passive"))
      (node (ref "JP66") (pin "2") (pinfunction "2_2") (pintype "passive"))
      (node (ref "JP67") (pin "2") (pinfunction "2_2") (pintype "passive"))
      (node (ref "JP68") (pin "2") (pinfunction "2_2") (pintype "passive"))
      (node (ref "JP69") (pin "2") (pinfunction "2_2") (pintype "passive"))
      (node (ref "JP7") (pin "2") (pinfunction "2_2") (pintype "passive"))
      (node (ref "JP70") (pin "2") (pinfunction "2_2") (pintype "passive"))
      (node (ref "JP71") (pin "2") (pinfunction "2_2") (pintype "passive"))
      (node (ref "JP72") (pin "2") (pinfunction "2_2") (pintype "passive"))
      (node (ref "JP73") (pin "2") (pinfunction "2_2") (pintype "passive"))
      (node (ref "JP8") (pin "2") (pinfunction "2_2") (pintype "passive"))
      (node (ref "JP9") (pin "2") (pinfunction "2_2") (pintype "passive"))
    )
  )
)
